# SNES.net
KiCad netlist of a schematic drawn in EAGLE
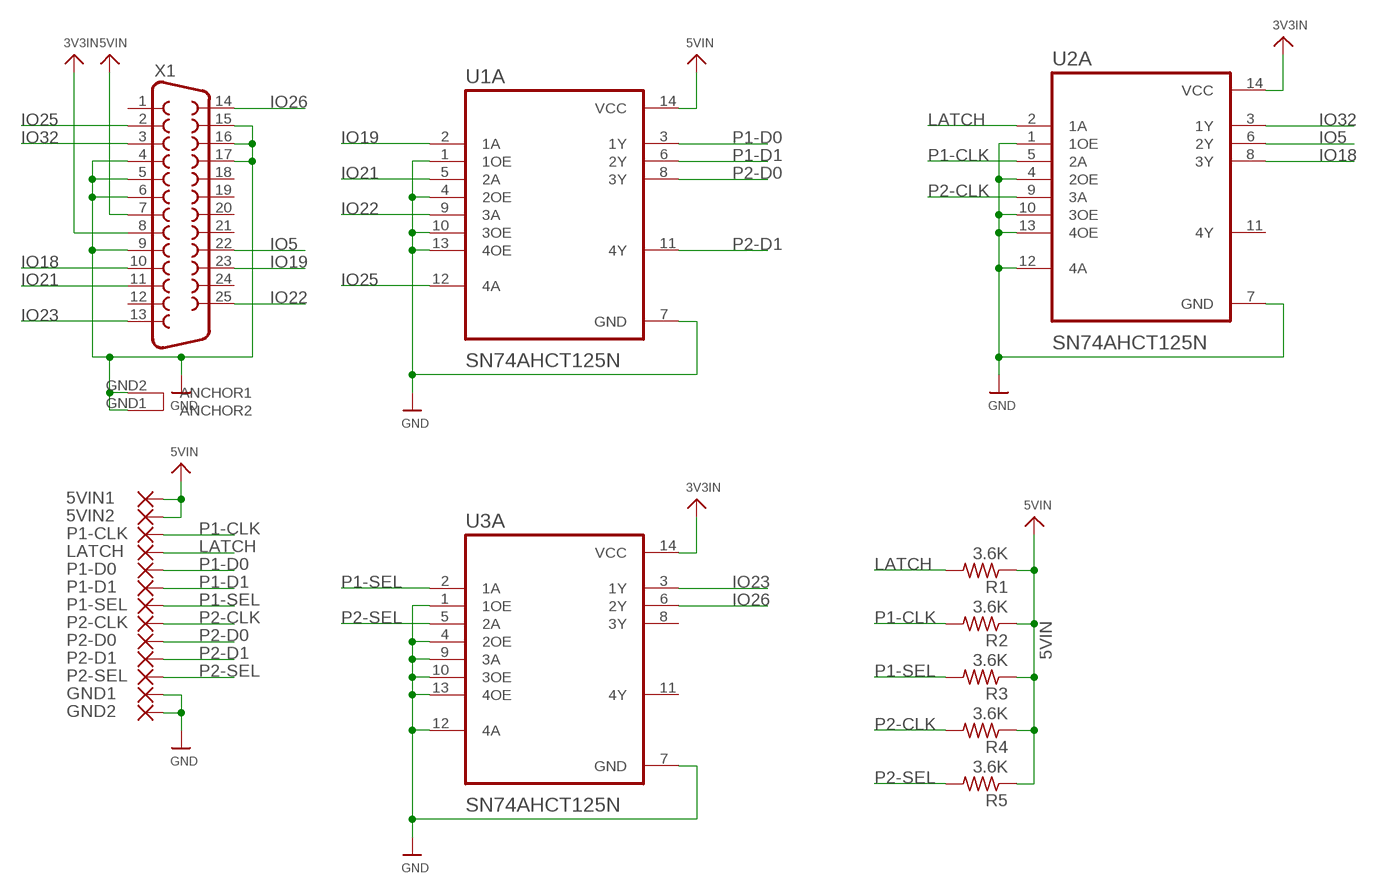
[diagram p0: schematic, sheet 1]

(export (version "E")
  (design (tool "Eeschema 10.0.6"))
  (components
    (comp (ref "5VIN1")
      (value "SMD5")
      (footprint "eagle-import:SMD2,54-5,08")
      (libsource (lib "eagle-import") (part "SMD5"))
    )
    (comp (ref "5VIN2")
      (value "SMD5")
      (footprint "eagle-import:SMD2,54-5,08")
      (libsource (lib "eagle-import") (part "SMD5"))
    )
    (comp (ref "GND1")
      (value "SMD5")
      (footprint "eagle-import:SMD2,54-5,08")
      (libsource (lib "eagle-import") (part "SMD5"))
    )
    (comp (ref "GND2")
      (value "SMD5")
      (footprint "eagle-import:SMD2,54-5,08")
      (libsource (lib "eagle-import") (part "SMD5"))
    )
    (comp (ref "LATCH")
      (value "SMD5")
      (footprint "eagle-import:SMD2,54-5,08")
      (libsource (lib "eagle-import") (part "SMD5"))
    )
    (comp (ref "P1-CLK")
      (value "SMD5")
      (footprint "eagle-import:SMD2,54-5,08")
      (libsource (lib "eagle-import") (part "SMD5"))
    )
    (comp (ref "P1-D0")
      (value "SMD5")
      (footprint "eagle-import:SMD2,54-5,08")
      (libsource (lib "eagle-import") (part "SMD5"))
    )
    (comp (ref "P1-D1")
      (value "SMD5")
      (footprint "eagle-import:SMD2,54-5,08")
      (libsource (lib "eagle-import") (part "SMD5"))
    )
    (comp (ref "P1-SEL")
      (value "SMD5")
      (footprint "eagle-import:SMD2,54-5,08")
      (libsource (lib "eagle-import") (part "SMD5"))
    )
    (comp (ref "P2-CLK")
      (value "SMD5")
      (footprint "eagle-import:SMD2,54-5,08")
      (libsource (lib "eagle-import") (part "SMD5"))
    )
    (comp (ref "P2-D0")
      (value "SMD5")
      (footprint "eagle-import:SMD2,54-5,08")
      (libsource (lib "eagle-import") (part "SMD5"))
    )
    (comp (ref "P2-D1")
      (value "SMD5")
      (footprint "eagle-import:SMD2,54-5,08")
      (libsource (lib "eagle-import") (part "SMD5"))
    )
    (comp (ref "P2-SEL")
      (value "SMD5")
      (footprint "eagle-import:SMD2,54-5,08")
      (libsource (lib "eagle-import") (part "SMD5"))
    )
    (comp (ref "R1")
      (value "3.6K")
      (footprint "eagle-import:R1206")
      (libsource (lib "eagle-import") (part "R-US_R1206"))
    )
    (comp (ref "R2")
      (value "3.6K")
      (footprint "eagle-import:R1206")
      (libsource (lib "eagle-import") (part "R-US_R1206"))
    )
    (comp (ref "R3")
      (value "3.6K")
      (footprint "eagle-import:R1206")
      (libsource (lib "eagle-import") (part "R-US_R1206"))
    )
    (comp (ref "R4")
      (value "3.6K")
      (footprint "eagle-import:R1206")
      (libsource (lib "eagle-import") (part "R-US_R1206"))
    )
    (comp (ref "R5")
      (value "3.6K")
      (footprint "eagle-import:R1206")
      (libsource (lib "eagle-import") (part "R-US_R1206"))
    )
    (comp (ref "U1A")
      (value "SN74AHCT125N")
      (footprint "eagle-import:DIP794W45P254L1969H508Q14")
      (fields (field (name "MF") "Texas Instruments"))
      (libsource (lib "eagle-import") (part "SN74AHCT125N"))
    )
    (comp (ref "U2A")
      (value "SN74AHCT125N")
      (footprint "eagle-import:DIP794W45P254L1969H508Q14")
      (fields (field (name "MF") "Texas Instruments"))
      (libsource (lib "eagle-import") (part "SN74AHCT125N"))
    )
    (comp (ref "U3A")
      (value "SN74AHCT125N")
      (footprint "eagle-import:DIP794W45P254L1969H508Q14")
      (fields (field (name "MF") "Texas Instruments"))
      (libsource (lib "eagle-import") (part "SN74AHCT125N"))
    )
    (comp (ref "X1")
      (value "DB25_FEMALEHP")
      (footprint "eagle-import:F25HP")
      (libsource (lib "eagle-import") (part "DB25_FEMALEHP"))
    )
  )
  (nets
    (net (code "1") (name "/IO5") (class "Default")
      (node (ref "U2A") (pin "6") (pinfunction "2Y_6") (pintype "output"))
      (node (ref "X1") (pin "22") (pinfunction "22_22") (pintype "passive"))
    )
    (net (code "2") (name "/IO18") (class "Default")
      (node (ref "U2A") (pin "8") (pinfunction "3Y_8") (pintype "output"))
      (node (ref "X1") (pin "10") (pinfunction "10_10") (pintype "passive"))
    )
    (net (code "3") (name "/IO19") (class "Default")
      (node (ref "U1A") (pin "2") (pinfunction "1A_2") (pintype "input"))
      (node (ref "X1") (pin "23") (pinfunction "23_23") (pintype "passive"))
    )
    (net (code "4") (name "/IO21") (class "Default")
      (node (ref "U1A") (pin "5") (pinfunction "2A_5") (pintype "input"))
      (node (ref "X1") (pin "11") (pinfunction "11_11") (pintype "passive"))
    )
    (net (code "5") (name "/IO22") (class "Default")
      (node (ref "U1A") (pin "9") (pinfunction "3A_9") (pintype "input"))
      (node (ref "X1") (pin "25") (pinfunction "25_25") (pintype "passive"))
    )
    (net (code "6") (name "/IO23") (class "Default")
      (node (ref "U3A") (pin "3") (pinfunction "1Y_3") (pintype "output"))
      (node (ref "X1") (pin "13") (pinfunction "13_13") (pintype "passive"))
    )
    (net (code "7") (name "/IO25") (class "Default")
      (node (ref "U1A") (pin "12") (pinfunction "4A_12") (pintype "bidirectional"))
      (node (ref "X1") (pin "2") (pinfunction "2_2") (pintype "passive"))
    )
    (net (code "8") (name "/IO26") (class "Default")
      (node (ref "U3A") (pin "6") (pinfunction "2Y_6") (pintype "output"))
      (node (ref "X1") (pin "14") (pinfunction "14_14") (pintype "passive"))
    )
    (net (code "9") (name "/IO32") (class "Default")
      (node (ref "U2A") (pin "3") (pinfunction "1Y_3") (pintype "output"))
      (node (ref "X1") (pin "3") (pinfunction "3_3") (pintype "passive"))
    )
    (net (code "10") (name "/LATCH") (class "Default")
      (node (ref "LATCH") (pin "1") (pinfunction "P_1") (pintype "passive"))
      (node (ref "R1") (pin "2") (pinfunction "2_2") (pintype "passive"))
      (node (ref "U2A") (pin "2") (pinfunction "1A_2") (pintype "input"))
    )
    (net (code "11") (name "/P1-CLK") (class "Default")
      (node (ref "P1-CLK") (pin "1") (pinfunction "P_1") (pintype "passive"))
      (node (ref "R2") (pin "2") (pinfunction "2_2") (pintype "passive"))
      (node (ref "U2A") (pin "5") (pinfunction "2A_5") (pintype "input"))
    )
    (net (code "12") (name "/P1-D0") (class "Default")
      (node (ref "P1-D0") (pin "1") (pinfunction "P_1") (pintype "passive"))
      (node (ref "U1A") (pin "3") (pinfunction "1Y_3") (pintype "output"))
    )
    (net (code "13") (name "/P1-D1") (class "Default")
      (node (ref "P1-D1") (pin "1") (pinfunction "P_1") (pintype "passive"))
      (node (ref "U1A") (pin "6") (pinfunction "2Y_6") (pintype "output"))
    )
    (net (code "14") (name "/P1-SEL") (class "Default")
      (node (ref "P1-SEL") (pin "1") (pinfunction "P_1") (pintype "passive"))
      (node (ref "R3") (pin "2") (pinfunction "2_2") (pintype "passive"))
      (node (ref "U3A") (pin "2") (pinfunction "1A_2") (pintype "input"))
    )
    (net (code "15") (name "/P2-CLK") (class "Default")
      (node (ref "P2-CLK") (pin "1") (pinfunction "P_1") (pintype "passive"))
      (node (ref "R4") (pin "2") (pinfunction "2_2") (pintype "passive"))
      (node (ref "U2A") (pin "9") (pinfunction "3A_9") (pintype "input"))
    )
    (net (code "16") (name "/P2-D0") (class "Default")
      (node (ref "P2-D0") (pin "1") (pinfunction "P_1") (pintype "passive"))
      (node (ref "U1A") (pin "8") (pinfunction "3Y_8") (pintype "output"))
    )
    (net (code "17") (name "/P2-D1") (class "Default")
      (node (ref "P2-D1") (pin "1") (pinfunction "P_1") (pintype "passive"))
      (node (ref "U1A") (pin "11") (pinfunction "4Y_11") (pintype "output"))
    )
    (net (code "18") (name "/P2-SEL") (class "Default")
      (node (ref "P2-SEL") (pin "1") (pinfunction "P_1") (pintype "passive"))
      (node (ref "R5") (pin "2") (pinfunction "2_2") (pintype "passive"))
      (node (ref "U3A") (pin "5") (pinfunction "2A_5") (pintype "input"))
    )
    (net (code "19") (name "3V3IN") (class "Default")
      (node (ref "U2A") (pin "14") (pinfunction "VCC_14") (pintype "power_in"))
      (node (ref "U3A") (pin "14") (pinfunction "VCC_14") (pintype "power_in"))
      (node (ref "X1") (pin "8") (pinfunction "8_8") (pintype "passive"))
    )
    (net (code "20") (name "5VIN") (class "Default")
      (node (ref "5VIN1") (pin "1") (pinfunction "P_1") (pintype "passive"))
      (node (ref "5VIN2") (pin "1") (pinfunction "P_1") (pintype "passive"))
      (node (ref "R1") (pin "1") (pinfunction "1_1") (pintype "passive"))
      (node (ref "R2") (pin "1") (pinfunction "1_1") (pintype "passive"))
      (node (ref "R3") (pin "1") (pinfunction "1_1") (pintype "passive"))
      (node (ref "R4") (pin "1") (pinfunction "1_1") (pintype "passive"))
      (node (ref "R5") (pin "1") (pinfunction "1_1") (pintype "passive"))
      (node (ref "U1A") (pin "14") (pinfunction "VCC_14") (pintype "power_in"))
      (node (ref "X1") (pin "7") (pinfunction "7_7") (pintype "passive"))
    )
    (net (code "21") (name "GND") (class "Default")
      (node (ref "GND1") (pin "1") (pinfunction "P_1") (pintype "passive"))
      (node (ref "GND2") (pin "1") (pinfunction "P_1") (pintype "passive"))
      (node (ref "U1A") (pin "1") (pinfunction "1OE_1") (pintype "input"))
      (node (ref "U1A") (pin "10") (pinfunction "3OE_10") (pintype "input"))
      (node (ref "U1A") (pin "13") (pinfunction "4OE_13") (pintype "input"))
      (node (ref "U1A") (pin "4") (pinfunction "2OE_4") (pintype "input"))
      (node (ref "U1A") (pin "7") (pinfunction "GND_7") (pintype "power_in"))
      (node (ref "U2A") (pin "1") (pinfunction "1OE_1") (pintype "input"))
      (node (ref "U2A") (pin "10") (pinfunction "3OE_10") (pintype "input"))
      (node (ref "U2A") (pin "12") (pinfunction "4A_12") (pintype "bidirectional"))
      (node (ref "U2A") (pin "13") (pinfunction "4OE_13") (pintype "input"))
      (node (ref "U2A") (pin "4") (pinfunction "2OE_4") (pintype "input"))
      (node (ref "U2A") (pin "7") (pinfunction "GND_7") (pintype "power_in"))
      (node (ref "U3A") (pin "1") (pinfunction "1OE_1") (pintype "input"))
      (node (ref "U3A") (pin "10") (pinfunction "3OE_10") (pintype "input"))
      (node (ref "U3A") (pin "12") (pinfunction "4A_12") (pintype "bidirectional"))
      (node (ref "U3A") (pin "13") (pinfunction "4OE_13") (pintype "input"))
      (node (ref "U3A") (pin "4") (pinfunction "2OE_4") (pintype "input"))
      (node (ref "U3A") (pin "7") (pinfunction "GND_7") (pintype "power_in"))
      (node (ref "U3A") (pin "9") (pinfunction "3A_9") (pintype "input"))
      (node (ref "X1") (pin "15") (pinfunction "15_15") (pintype "passive"))
      (node (ref "X1") (pin "16") (pinfunction "16_16") (pintype "passive"))
      (node (ref "X1") (pin "17") (pinfunction "17_17") (pintype "passive"))
      (node (ref "X1") (pin "4") (pinfunction "4_4") (pintype "passive"))
      (node (ref "X1") (pin "5") (pinfunction "5_5") (pintype "passive"))
      (node (ref "X1") (pin "6") (pinfunction "6_6") (pintype "passive"))
      (node (ref "X1") (pin "9") (pinfunction "9_9") (pintype "passive"))
      (node (ref "X1") (pin "GND1") (pinfunction "ANCHOR2_GND1") (pintype "bidirectional"))
      (node (ref "X1") (pin "GND2") (pinfunction "ANCHOR1_GND2") (pintype "bidirectional"))
    )
    (net (code "22") (name "unconnected-(U2A-4Y-Pad11)") (class "Default")
      (node (ref "U2A") (pin "11") (pinfunction "4Y_11") (pintype "output"))
    )
    (net (code "23") (name "unconnected-(U3A-3Y-Pad8)") (class "Default")
      (node (ref "U3A") (pin "8") (pinfunction "3Y_8") (pintype "output"))
    )
    (net (code "24") (name "unconnected-(U3A-4Y-Pad11)") (class "Default")
      (node (ref "U3A") (pin "11") (pinfunction "4Y_11") (pintype "output"))
    )
    (net (code "25") (name "unconnected-(X1-Pad1)") (class "Default")
      (node (ref "X1") (pin "1") (pinfunction "1_1") (pintype "passive"))
    )
    (net (code "26") (name "unconnected-(X1-Pad12)") (class "Default")
      (node (ref "X1") (pin "12") (pinfunction "12_12") (pintype "passive"))
    )
    (net (code "27") (name "unconnected-(X1-Pad18)") (class "Default")
      (node (ref "X1") (pin "18") (pinfunction "18_18") (pintype "passive"))
    )
    (net (code "28") (name "unconnected-(X1-Pad19)") (class "Default")
      (node (ref "X1") (pin "19") (pinfunction "19_19") (pintype "passive"))
    )
    (net (code "29") (name "unconnected-(X1-Pad20)") (class "Default")
      (node (ref "X1") (pin "20") (pinfunction "20_20") (pintype "passive"))
    )
    (net (code "30") (name "unconnected-(X1-Pad21)") (class "Default")
      (node (ref "X1") (pin "21") (pinfunction "21_21") (pintype "passive"))
    )
    (net (code "31") (name "unconnected-(X1-Pad24)") (class "Default")
      (node (ref "X1") (pin "24") (pinfunction "24_24") (pintype "passive"))
    )
  )
)
